# MUX.net
KiCad netlist of a schematic drawn in Altium Designer
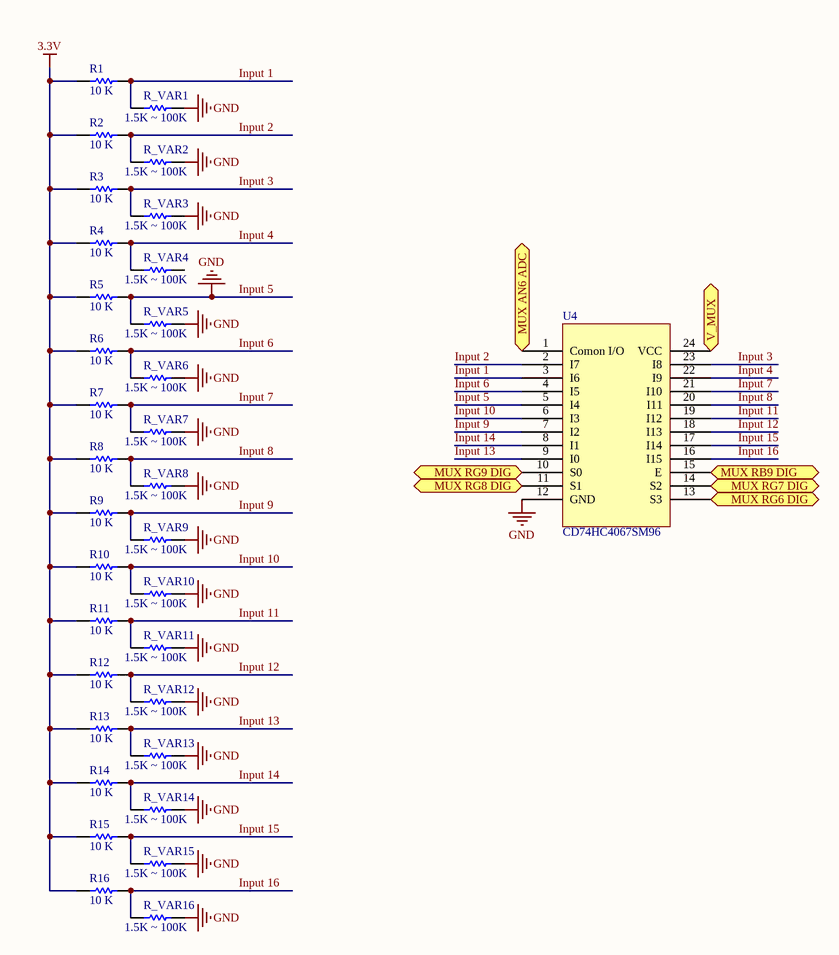
[diagram p0: MUX.SchDoc]

(export (version "E")
  (design (tool "Eeschema 10.0.6"))
  (components
    (comp (ref "R1")
      (value "10 K")
      (footprint "Resistor0603")
      (description "Resistor")
      (fields (field (name "PUBLISHER") "Altium Limited"))
      (libsource (lib "Miscellaneous Devices") (part "Res1"))
    )
    (comp (ref "R2")
      (value "10 K")
      (footprint "Resistor0603")
      (description "Resistor")
      (fields (field (name "PUBLISHER") "Altium Limited"))
      (libsource (lib "Miscellaneous Devices") (part "Res1"))
    )
    (comp (ref "R3")
      (value "10 K")
      (footprint "Resistor0603")
      (description "Resistor")
      (fields (field (name "PUBLISHER") "Altium Limited"))
      (libsource (lib "Miscellaneous Devices") (part "Res1"))
    )
    (comp (ref "R4")
      (value "10 K")
      (footprint "Resistor0603")
      (description "Resistor")
      (fields (field (name "PUBLISHER") "Altium Limited"))
      (libsource (lib "Miscellaneous Devices") (part "Res1"))
    )
    (comp (ref "R5")
      (value "10 K")
      (footprint "Resistor0603")
      (description "Resistor")
      (fields (field (name "PUBLISHER") "Altium Limited"))
      (libsource (lib "Miscellaneous Devices") (part "Res1"))
    )
    (comp (ref "R6")
      (value "10 K")
      (footprint "Resistor0603")
      (description "Resistor")
      (fields (field (name "PUBLISHER") "Altium Limited"))
      (libsource (lib "Miscellaneous Devices") (part "Res1"))
    )
    (comp (ref "R7")
      (value "10 K")
      (footprint "Resistor0603")
      (description "Resistor")
      (fields (field (name "PUBLISHER") "Altium Limited"))
      (libsource (lib "Miscellaneous Devices") (part "Res1"))
    )
    (comp (ref "R8")
      (value "10 K")
      (footprint "Resistor0603")
      (description "Resistor")
      (fields (field (name "PUBLISHER") "Altium Limited"))
      (libsource (lib "Miscellaneous Devices") (part "Res1"))
    )
    (comp (ref "R9")
      (value "10 K")
      (footprint "Resistor0603")
      (description "Resistor")
      (fields (field (name "PUBLISHER") "Altium Limited"))
      (libsource (lib "Miscellaneous Devices") (part "Res1"))
    )
    (comp (ref "R10")
      (value "10 K")
      (footprint "Resistor0603")
      (description "Resistor")
      (fields (field (name "PUBLISHER") "Altium Limited"))
      (libsource (lib "Miscellaneous Devices") (part "Res1"))
    )
    (comp (ref "R11")
      (value "10 K")
      (footprint "Resistor0603")
      (description "Resistor")
      (fields (field (name "PUBLISHER") "Altium Limited"))
      (libsource (lib "Miscellaneous Devices") (part "Res1"))
    )
    (comp (ref "R12")
      (value "10 K")
      (footprint "Resistor0603")
      (description "Resistor")
      (fields (field (name "PUBLISHER") "Altium Limited"))
      (libsource (lib "Miscellaneous Devices") (part "Res1"))
    )
    (comp (ref "R13")
      (value "10 K")
      (footprint "Resistor0603")
      (description "Resistor")
      (fields (field (name "PUBLISHER") "Altium Limited"))
      (libsource (lib "Miscellaneous Devices") (part "Res1"))
    )
    (comp (ref "R14")
      (value "10 K")
      (footprint "Resistor0603")
      (description "Resistor")
      (fields (field (name "PUBLISHER") "Altium Limited"))
      (libsource (lib "Miscellaneous Devices") (part "Res1"))
    )
    (comp (ref "R15")
      (value "10 K")
      (footprint "Resistor0603")
      (description "Resistor")
      (fields (field (name "PUBLISHER") "Altium Limited"))
      (libsource (lib "Miscellaneous Devices") (part "Res1"))
    )
    (comp (ref "R16")
      (value "10 K")
      (footprint "Resistor0603")
      (description "Resistor")
      (fields (field (name "PUBLISHER") "Altium Limited"))
      (libsource (lib "Miscellaneous Devices") (part "Res1"))
    )
    (comp (ref "R_VAR1")
      (value "1.5K ~ 100K")
      (footprint "OrderPiece")
      (description "Resistor")
      (fields (field (name "PUBLISHER") "Altium Limited"))
      (libsource (lib "Miscellaneous Devices") (part "Res1"))
    )
    (comp (ref "R_VAR2")
      (value "1.5K ~ 100K")
      (footprint "OrderPiece")
      (description "Resistor")
      (fields (field (name "PUBLISHER") "Altium Limited"))
      (libsource (lib "Miscellaneous Devices") (part "Res1"))
    )
    (comp (ref "R_VAR3")
      (value "1.5K ~ 100K")
      (footprint "OrderPiece")
      (description "Resistor")
      (fields (field (name "PUBLISHER") "Altium Limited"))
      (libsource (lib "Miscellaneous Devices") (part "Res1"))
    )
    (comp (ref "R_VAR4")
      (value "1.5K ~ 100K")
      (footprint "OrderPiece")
      (description "Resistor")
      (fields (field (name "PUBLISHER") "Altium Limited"))
      (libsource (lib "Miscellaneous Devices") (part "Res1"))
    )
    (comp (ref "R_VAR5")
      (value "1.5K ~ 100K")
      (footprint "OrderPiece")
      (description "Resistor")
      (fields (field (name "PUBLISHER") "Altium Limited"))
      (libsource (lib "Miscellaneous Devices") (part "Res1"))
    )
    (comp (ref "R_VAR6")
      (value "1.5K ~ 100K")
      (footprint "OrderPiece")
      (description "Resistor")
      (fields (field (name "PUBLISHER") "Altium Limited"))
      (libsource (lib "Miscellaneous Devices") (part "Res1"))
    )
    (comp (ref "R_VAR7")
      (value "1.5K ~ 100K")
      (footprint "OrderPiece")
      (description "Resistor")
      (fields (field (name "PUBLISHER") "Altium Limited"))
      (libsource (lib "Miscellaneous Devices") (part "Res1"))
    )
    (comp (ref "R_VAR8")
      (value "1.5K ~ 100K")
      (footprint "OrderPiece")
      (description "Resistor")
      (fields (field (name "PUBLISHER") "Altium Limited"))
      (libsource (lib "Miscellaneous Devices") (part "Res1"))
    )
    (comp (ref "R_VAR9")
      (value "1.5K ~ 100K")
      (footprint "OrderPiece")
      (description "Resistor")
      (fields (field (name "PUBLISHER") "Altium Limited"))
      (libsource (lib "Miscellaneous Devices") (part "Res1"))
    )
    (comp (ref "R_VAR10")
      (value "1.5K ~ 100K")
      (footprint "OrderPiece")
      (description "Resistor")
      (fields (field (name "PUBLISHER") "Altium Limited"))
      (libsource (lib "Miscellaneous Devices") (part "Res1"))
    )
    (comp (ref "R_VAR11")
      (value "1.5K ~ 100K")
      (footprint "OrderPiece")
      (description "Resistor")
      (fields (field (name "PUBLISHER") "Altium Limited"))
      (libsource (lib "Miscellaneous Devices") (part "Res1"))
    )
    (comp (ref "R_VAR12")
      (value "1.5K ~ 100K")
      (footprint "OrderPiece")
      (description "Resistor")
      (fields (field (name "PUBLISHER") "Altium Limited"))
      (libsource (lib "Miscellaneous Devices") (part "Res1"))
    )
    (comp (ref "R_VAR13")
      (value "1.5K ~ 100K")
      (footprint "OrderPiece")
      (description "Resistor")
      (fields (field (name "PUBLISHER") "Altium Limited"))
      (libsource (lib "Miscellaneous Devices") (part "Res1"))
    )
    (comp (ref "R_VAR14")
      (value "1.5K ~ 100K")
      (footprint "OrderPiece")
      (description "Resistor")
      (fields (field (name "PUBLISHER") "Altium Limited"))
      (libsource (lib "Miscellaneous Devices") (part "Res1"))
    )
    (comp (ref "R_VAR15")
      (value "1.5K ~ 100K")
      (footprint "OrderPiece")
      (description "Resistor")
      (fields (field (name "PUBLISHER") "Altium Limited"))
      (libsource (lib "Miscellaneous Devices") (part "Res1"))
    )
    (comp (ref "R_VAR16")
      (value "1.5K ~ 100K")
      (footprint "OrderPiece")
      (description "Resistor")
      (fields (field (name "PUBLISHER") "Altium Limited"))
      (libsource (lib "Miscellaneous Devices") (part "Res1"))
    )
    (comp (ref "U4")
      (value "CD74HC4067SM96")
      (footprint "MUX")
      (libsource (lib "PROBOT_Schema_Library") (part "Analog Multiplexor"))
    )
  )
  (nets
    (net (code "1") (name "/Input 1") (class "Default")
      (node (ref "R1") (pin "2") (pinfunction "2_2") (pintype "passive"))
      (node (ref "R_VAR1") (pin "1") (pinfunction "1_1") (pintype "passive"))
      (node (ref "U4") (pin "3") (pinfunction "I6_3") (pintype "passive"))
    )
    (net (code "2") (name "/Input 2") (class "Default")
      (node (ref "R2") (pin "2") (pinfunction "2_2") (pintype "passive"))
      (node (ref "R_VAR2") (pin "1") (pinfunction "1_1") (pintype "passive"))
      (node (ref "U4") (pin "2") (pinfunction "I7_2") (pintype "passive"))
    )
    (net (code "3") (name "/Input 3") (class "Default")
      (node (ref "R3") (pin "2") (pinfunction "2_2") (pintype "passive"))
      (node (ref "R_VAR3") (pin "1") (pinfunction "1_1") (pintype "passive"))
      (node (ref "U4") (pin "23") (pinfunction "I8_23") (pintype "passive"))
    )
    (net (code "4") (name "/Input 4") (class "Default")
      (node (ref "R4") (pin "2") (pinfunction "2_2") (pintype "passive"))
      (node (ref "R_VAR4") (pin "1") (pinfunction "1_1") (pintype "passive"))
      (node (ref "U4") (pin "22") (pinfunction "I9_22") (pintype "passive"))
    )
    (net (code "5") (name "/Input 6") (class "Default")
      (node (ref "R6") (pin "2") (pinfunction "2_2") (pintype "passive"))
      (node (ref "R_VAR6") (pin "1") (pinfunction "1_1") (pintype "passive"))
      (node (ref "U4") (pin "4") (pinfunction "I5_4") (pintype "passive"))
    )
    (net (code "6") (name "/Input 7") (class "Default")
      (node (ref "R7") (pin "2") (pinfunction "2_2") (pintype "passive"))
      (node (ref "R_VAR7") (pin "1") (pinfunction "1_1") (pintype "passive"))
      (node (ref "U4") (pin "21") (pinfunction "I10_21") (pintype "passive"))
    )
    (net (code "7") (name "/Input 8") (class "Default")
      (node (ref "R8") (pin "2") (pinfunction "2_2") (pintype "passive"))
      (node (ref "R_VAR8") (pin "1") (pinfunction "1_1") (pintype "passive"))
      (node (ref "U4") (pin "20") (pinfunction "I11_20") (pintype "passive"))
    )
    (net (code "8") (name "/Input 9") (class "Default")
      (node (ref "R9") (pin "2") (pinfunction "2_2") (pintype "passive"))
      (node (ref "R_VAR9") (pin "1") (pinfunction "1_1") (pintype "passive"))
      (node (ref "U4") (pin "7") (pinfunction "I2_7") (pintype "passive"))
    )
    (net (code "9") (name "/Input 10") (class "Default")
      (node (ref "R10") (pin "2") (pinfunction "2_2") (pintype "passive"))
      (node (ref "R_VAR10") (pin "1") (pinfunction "1_1") (pintype "passive"))
      (node (ref "U4") (pin "6") (pinfunction "I3_6") (pintype "passive"))
    )
    (net (code "10") (name "/Input 11") (class "Default")
      (node (ref "R11") (pin "2") (pinfunction "2_2") (pintype "passive"))
      (node (ref "R_VAR11") (pin "1") (pinfunction "1_1") (pintype "passive"))
      (node (ref "U4") (pin "19") (pinfunction "I12_19") (pintype "passive"))
    )
    (net (code "11") (name "/Input 12") (class "Default")
      (node (ref "R12") (pin "2") (pinfunction "2_2") (pintype "passive"))
      (node (ref "R_VAR12") (pin "1") (pinfunction "1_1") (pintype "passive"))
      (node (ref "U4") (pin "18") (pinfunction "I13_18") (pintype "passive"))
    )
    (net (code "12") (name "/Input 13") (class "Default")
      (node (ref "R13") (pin "2") (pinfunction "2_2") (pintype "passive"))
      (node (ref "R_VAR13") (pin "1") (pinfunction "1_1") (pintype "passive"))
      (node (ref "U4") (pin "9") (pinfunction "I0_9") (pintype "passive"))
    )
    (net (code "13") (name "/Input 14") (class "Default")
      (node (ref "R14") (pin "2") (pinfunction "2_2") (pintype "passive"))
      (node (ref "R_VAR14") (pin "1") (pinfunction "1_1") (pintype "passive"))
      (node (ref "U4") (pin "8") (pinfunction "I1_8") (pintype "passive"))
    )
    (net (code "14") (name "/Input 15") (class "Default")
      (node (ref "R15") (pin "2") (pinfunction "2_2") (pintype "passive"))
      (node (ref "R_VAR15") (pin "1") (pinfunction "1_1") (pintype "passive"))
      (node (ref "U4") (pin "17") (pinfunction "I14_17") (pintype "passive"))
    )
    (net (code "15") (name "/Input 16") (class "Default")
      (node (ref "R16") (pin "2") (pinfunction "2_2") (pintype "passive"))
      (node (ref "R_VAR16") (pin "1") (pinfunction "1_1") (pintype "passive"))
      (node (ref "U4") (pin "16") (pinfunction "I15_16") (pintype "passive"))
    )
    (net (code "16") (name "/MUX AN6 ADC") (class "Default")
      (node (ref "U4") (pin "1") (pinfunction "Comon_I/O_1") (pintype "passive"))
    )
    (net (code "17") (name "/MUX RB9 DIG") (class "Default")
      (node (ref "U4") (pin "15") (pinfunction "E_15") (pintype "passive"))
    )
    (net (code "18") (name "/MUX RG6 DIG") (class "Default")
      (node (ref "U4") (pin "13") (pinfunction "S3_13") (pintype "passive"))
    )
    (net (code "19") (name "/MUX RG7 DIG") (class "Default")
      (node (ref "U4") (pin "14") (pinfunction "S2_14") (pintype "passive"))
    )
    (net (code "20") (name "/MUX RG8 DIG") (class "Default")
      (node (ref "U4") (pin "11") (pinfunction "S1_11") (pintype "passive"))
    )
    (net (code "21") (name "/MUX RG9 DIG") (class "Default")
      (node (ref "U4") (pin "10") (pinfunction "S0_10") (pintype "passive"))
    )
    (net (code "22") (name "/V_MUX") (class "Default")
      (node (ref "U4") (pin "24") (pinfunction "VCC_24") (pintype "passive"))
    )
    (net (code "23") (name "3.3V") (class "Default")
      (node (ref "R1") (pin "1") (pinfunction "1_1") (pintype "passive"))
      (node (ref "R10") (pin "1") (pinfunction "1_1") (pintype "passive"))
      (node (ref "R11") (pin "1") (pinfunction "1_1") (pintype "passive"))
      (node (ref "R12") (pin "1") (pinfunction "1_1") (pintype "passive"))
      (node (ref "R13") (pin "1") (pinfunction "1_1") (pintype "passive"))
      (node (ref "R14") (pin "1") (pinfunction "1_1") (pintype "passive"))
      (node (ref "R15") (pin "1") (pinfunction "1_1") (pintype "passive"))
      (node (ref "R16") (pin "1") (pinfunction "1_1") (pintype "passive"))
      (node (ref "R2") (pin "1") (pinfunction "1_1") (pintype "passive"))
      (node (ref "R3") (pin "1") (pinfunction "1_1") (pintype "passive"))
      (node (ref "R4") (pin "1") (pinfunction "1_1") (pintype "passive"))
      (node (ref "R5") (pin "1") (pinfunction "1_1") (pintype "passive"))
      (node (ref "R6") (pin "1") (pinfunction "1_1") (pintype "passive"))
      (node (ref "R7") (pin "1") (pinfunction "1_1") (pintype "passive"))
      (node (ref "R8") (pin "1") (pinfunction "1_1") (pintype "passive"))
      (node (ref "R9") (pin "1") (pinfunction "1_1") (pintype "passive"))
    )
    (net (code "24") (name "GND") (class "Default")
      (node (ref "R5") (pin "2") (pinfunction "2_2") (pintype "passive"))
      (node (ref "R_VAR1") (pin "2") (pinfunction "2_2") (pintype "passive"))
      (node (ref "R_VAR10") (pin "2") (pinfunction "2_2") (pintype "passive"))
      (node (ref "R_VAR11") (pin "2") (pinfunction "2_2") (pintype "passive"))
      (node (ref "R_VAR12") (pin "2") (pinfunction "2_2") (pintype "passive"))
      (node (ref "R_VAR13") (pin "2") (pinfunction "2_2") (pintype "passive"))
      (node (ref "R_VAR14") (pin "2") (pinfunction "2_2") (pintype "passive"))
      (node (ref "R_VAR15") (pin "2") (pinfunction "2_2") (pintype "passive"))
      (node (ref "R_VAR16") (pin "2") (pinfunction "2_2") (pintype "passive"))
      (node (ref "R_VAR2") (pin "2") (pinfunction "2_2") (pintype "passive"))
      (node (ref "R_VAR3") (pin "2") (pinfunction "2_2") (pintype "passive"))
      (node (ref "R_VAR5") (pin "1") (pinfunction "1_1") (pintype "passive"))
      (node (ref "R_VAR5") (pin "2") (pinfunction "2_2") (pintype "passive"))
      (node (ref "R_VAR6") (pin "2") (pinfunction "2_2") (pintype "passive"))
      (node (ref "R_VAR7") (pin "2") (pinfunction "2_2") (pintype "passive"))
      (node (ref "R_VAR8") (pin "2") (pinfunction "2_2") (pintype "passive"))
      (node (ref "R_VAR9") (pin "2") (pinfunction "2_2") (pintype "passive"))
      (node (ref "U4") (pin "12") (pinfunction "GND_12") (pintype "passive"))
      (node (ref "U4") (pin "5") (pinfunction "I4_5") (pintype "passive"))
    )
    (net (code "25") (name "unconnected-(R_VAR4-Pad2)") (class "Default")
      (node (ref "R_VAR4") (pin "2") (pinfunction "2_2") (pintype "passive"))
    )
  )
)
